# LightLinkV2.net
KiCad netlist of a schematic drawn in Altium Designer
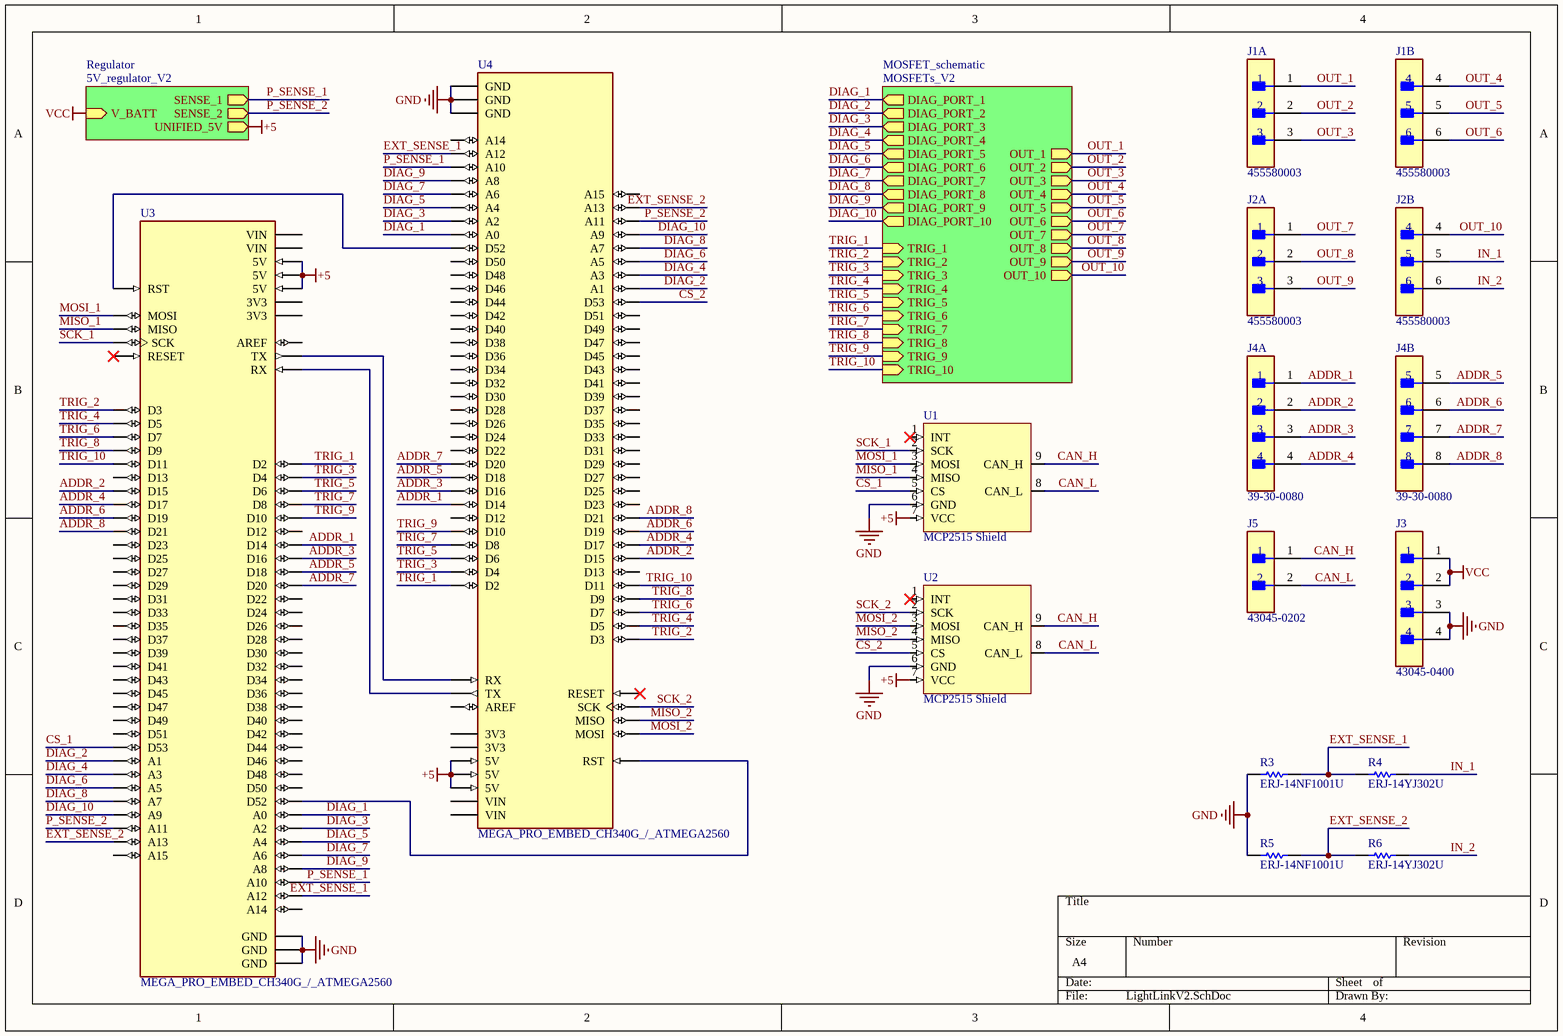
[diagram p0: LightLinkV2.SchDoc]

(export (version "E")
  (design (tool "Eeschema 10.0.6"))
  (components
    (comp (ref "J1")
      (value "455580003")
      (footprint "FP-455580003-MFG")
      (description "Connector Header Through Hole, Right Angle 6 position 0.165\" (4.20mm)")
      (fields (field (name "OCTOPART") "https://octopart.com/45558-0003-molex-7672845"))
      (libsource (lib "Altium Content Vault") (part "bb9cbdb24149a20ba329b4e86909569"))
    )
    (comp (ref "J2")
      (value "455580003")
      (footprint "FP-455580003-MFG")
      (description "Connector Header Through Hole, Right Angle 6 position 0.165\" (4.20mm)")
      (fields (field (name "OCTOPART") "https://octopart.com/45558-0003-molex-7672845"))
      (libsource (lib "Altium Content Vault") (part "bb9cbdb24149a20ba329b4e86909569"))
    )
    (comp (ref "J3")
      (value "43045-0400")
      (footprint "FP-43045-0400-MFG")
      (description "CONN HEADER R/A 4POS 3MM")
      (fields
        (field (name "MANUFACTURER") "Molex")
        (field (name "OCTOPART") "https://octopart.com/43045-0400-molex-287063")
      )
      (libsource (lib "Altium Content Vault") (part "c01754ab0efc13afb7424b896f394ef"))
    )
    (comp (ref "J4")
      (value "39-30-0080")
      (footprint "FP-39-30-0080-MFG")
      (description "CONN HEADER R/A 8POS 4.2MM")
      (libsource (lib "Altium Content Vault") (part "85438c39ca9ef07d43bb2e97c52bc44"))
    )
    (comp (ref "J5")
      (value "43045-0202")
      (footprint "FP-43045-0202-MFG")
      (description "CONN HEADER R/A 2POS")
      (libsource (lib "Altium Content Vault") (part "3bc925449376181038e59eaffc5286c"))
    )
    (comp (ref "R3")
      (value "ERJ-14NF1001U")
      (footprint "RESC3225X70X50NL20T20")
      (fields (field (name "MANUFACTURER") "Panasonic"))
      (libsource (lib "Altium Content Vault") (part "RES"))
    )
    (comp (ref "R4")
      (value "ERJ-14YJ302U")
      (footprint "RESC3225X70X50NL20T20")
      (fields (field (name "MANUFACTURER") "Panasonic"))
      (libsource (lib "Altium Content Vault") (part "RES"))
    )
    (comp (ref "R5")
      (value "ERJ-14NF1001U")
      (footprint "RESC3225X70X50NL20T20")
      (fields (field (name "MANUFACTURER") "Panasonic"))
      (libsource (lib "Altium Content Vault") (part "RES"))
    )
    (comp (ref "R6")
      (value "ERJ-14YJ302U")
      (footprint "RESC3225X70X50NL20T20")
      (fields (field (name "MANUFACTURER") "Panasonic"))
      (libsource (lib "Altium Content Vault") (part "RES"))
    )
    (comp (ref "U1")
      (value "MCP2515 Shield")
      (footprint "MCP2515 Shield-Footprint-1")
      (libsource (lib "uORocketry Hardware") (part "MCP2515 Shield Symbol"))
    )
    (comp (ref "U2")
      (value "MCP2515 Shield")
      (footprint "MCP2515 Shield-Footprint-1")
      (libsource (lib "uORocketry Hardware") (part "MCP2515 Shield Symbol"))
    )
    (comp (ref "U3")
      (value "MEGA_PRO_EMBED_CH340G_/_ATMEGA2560")
      (footprint "MODULE_MEGA_PRO_EMBED_CH340G_/_ATMEGA2560")
      (description "Mega 2560 PRO (Embed) CH340G/ATmega2560-16AU")
      (libsource (lib "uORocketry Hardware") (part "MEGA_PRO_EMBED_CH340G_/_ATMEGA2560"))
    )
    (comp (ref "U4")
      (value "MEGA_PRO_EMBED_CH340G_/_ATMEGA2560")
      (footprint "MODULE_MEGA_PRO_EMBED_CH340G_/_ATMEGA2560")
      (description "Mega 2560 PRO (Embed) CH340G/ATmega2560-16AU")
      (libsource (lib "") (part "MEGA_PRO_EMBED_CH340G_/_ATMEGA2560_1"))
    )
  )
  (nets
    (net (code "1") (name "+5") (class "Default")
      (node (ref "U1") (pin "7") (pinfunction "VCC_7") (pintype "input"))
      (node (ref "U2") (pin "7") (pinfunction "VCC_7") (pintype "input"))
      (node (ref "U3") (pin "5V_1") (pinfunction "5V_5V_1") (pintype "input"))
      (node (ref "U3") (pin "5V_2") (pinfunction "5V_5V_2") (pintype "input"))
      (node (ref "U3") (pin "5V_3") (pinfunction "5V_5V_3") (pintype "input"))
      (node (ref "U4") (pin "5V_1") (pinfunction "5V_5V_1") (pintype "input"))
      (node (ref "U4") (pin "5V_2") (pinfunction "5V_5V_2") (pintype "input"))
      (node (ref "U4") (pin "5V_3") (pinfunction "5V_5V_3") (pintype "input"))
    )
    (net (code "2") (name "/ADDR_1") (class "Default")
      (node (ref "J4") (pin "1") (pinfunction "1_1") (pintype "passive"))
      (node (ref "U3") (pin "D14") (pinfunction "D14_D14") (pintype "bidirectional"))
      (node (ref "U4") (pin "D14") (pinfunction "D14_D14") (pintype "bidirectional"))
    )
    (net (code "3") (name "/ADDR_2") (class "Default")
      (node (ref "J4") (pin "2") (pinfunction "2_2") (pintype "passive"))
      (node (ref "U3") (pin "D15") (pinfunction "D15_D15") (pintype "bidirectional"))
      (node (ref "U4") (pin "D15") (pinfunction "D15_D15") (pintype "bidirectional"))
    )
    (net (code "4") (name "/ADDR_3") (class "Default")
      (node (ref "J4") (pin "3") (pinfunction "3_3") (pintype "passive"))
      (node (ref "U3") (pin "D16") (pinfunction "D16_D16") (pintype "bidirectional"))
      (node (ref "U4") (pin "D16") (pinfunction "D16_D16") (pintype "bidirectional"))
    )
    (net (code "5") (name "/ADDR_4") (class "Default")
      (node (ref "J4") (pin "4") (pinfunction "4_4") (pintype "passive"))
      (node (ref "U3") (pin "D17") (pinfunction "D17_D17") (pintype "bidirectional"))
      (node (ref "U4") (pin "D17") (pinfunction "D17_D17") (pintype "bidirectional"))
    )
    (net (code "6") (name "/ADDR_5") (class "Default")
      (node (ref "J4") (pin "5") (pinfunction "5_5") (pintype "passive"))
      (node (ref "U3") (pin "D18") (pinfunction "D18_D18") (pintype "bidirectional"))
      (node (ref "U4") (pin "D18") (pinfunction "D18_D18") (pintype "bidirectional"))
    )
    (net (code "7") (name "/ADDR_6") (class "Default")
      (node (ref "J4") (pin "6") (pinfunction "6_6") (pintype "passive"))
      (node (ref "U3") (pin "D19") (pinfunction "D19_D19") (pintype "bidirectional"))
      (node (ref "U4") (pin "D19") (pinfunction "D19_D19") (pintype "bidirectional"))
    )
    (net (code "8") (name "/ADDR_7") (class "Default")
      (node (ref "J4") (pin "7") (pinfunction "7_7") (pintype "passive"))
      (node (ref "U3") (pin "D20") (pinfunction "D20_D20") (pintype "bidirectional"))
      (node (ref "U4") (pin "D20") (pinfunction "D20_D20") (pintype "bidirectional"))
    )
    (net (code "9") (name "/ADDR_8") (class "Default")
      (node (ref "J4") (pin "8") (pinfunction "8_8") (pintype "passive"))
      (node (ref "U3") (pin "D21") (pinfunction "D21_D21") (pintype "bidirectional"))
      (node (ref "U4") (pin "D21") (pinfunction "D21_D21") (pintype "bidirectional"))
    )
    (net (code "10") (name "/CAN_H") (class "Default")
      (node (ref "J5") (pin "1") (pinfunction "1_1") (pintype "passive"))
      (node (ref "U1") (pin "9") (pinfunction "CAN_H_9") (pintype "bidirectional"))
      (node (ref "U2") (pin "9") (pinfunction "CAN_H_9") (pintype "bidirectional"))
    )
    (net (code "11") (name "/CAN_L") (class "Default")
      (node (ref "J5") (pin "2") (pinfunction "2_2") (pintype "passive"))
      (node (ref "U1") (pin "8") (pinfunction "CAN_L_8") (pintype "bidirectional"))
      (node (ref "U2") (pin "8") (pinfunction "CAN_L_8") (pintype "bidirectional"))
    )
    (net (code "12") (name "/CS_1") (class "Default")
      (node (ref "U1") (pin "5") (pinfunction "CS_5") (pintype "input"))
      (node (ref "U3") (pin "D53") (pinfunction "D53_D53") (pintype "bidirectional"))
    )
    (net (code "13") (name "/CS_2") (class "Default")
      (node (ref "U2") (pin "5") (pinfunction "CS_5") (pintype "input"))
      (node (ref "U4") (pin "D53") (pinfunction "D53_D53") (pintype "bidirectional"))
    )
    (net (code "14") (name "/DIAG_1") (class "Default")
      (node (ref "U3") (pin "A0") (pinfunction "A0_A0") (pintype "bidirectional"))
      (node (ref "U4") (pin "A0") (pinfunction "A0_A0") (pintype "bidirectional"))
    )
    (net (code "15") (name "/DIAG_2") (class "Default")
      (node (ref "U3") (pin "A1") (pinfunction "A1_A1") (pintype "bidirectional"))
      (node (ref "U4") (pin "A1") (pinfunction "A1_A1") (pintype "bidirectional"))
    )
    (net (code "16") (name "/DIAG_3") (class "Default")
      (node (ref "U3") (pin "A2") (pinfunction "A2_A2") (pintype "bidirectional"))
      (node (ref "U4") (pin "A2") (pinfunction "A2_A2") (pintype "bidirectional"))
    )
    (net (code "17") (name "/DIAG_4") (class "Default")
      (node (ref "U3") (pin "A3") (pinfunction "A3_A3") (pintype "bidirectional"))
      (node (ref "U4") (pin "A3") (pinfunction "A3_A3") (pintype "bidirectional"))
    )
    (net (code "18") (name "/DIAG_5") (class "Default")
      (node (ref "U3") (pin "A4") (pinfunction "A4_A4") (pintype "bidirectional"))
      (node (ref "U4") (pin "A4") (pinfunction "A4_A4") (pintype "bidirectional"))
    )
    (net (code "19") (name "/DIAG_6") (class "Default")
      (node (ref "U3") (pin "A5") (pinfunction "A5_A5") (pintype "bidirectional"))
      (node (ref "U4") (pin "A5") (pinfunction "A5_A5") (pintype "bidirectional"))
    )
    (net (code "20") (name "/DIAG_7") (class "Default")
      (node (ref "U3") (pin "A6") (pinfunction "A6_A6") (pintype "bidirectional"))
      (node (ref "U4") (pin "A6") (pinfunction "A6_A6") (pintype "bidirectional"))
    )
    (net (code "21") (name "/DIAG_8") (class "Default")
      (node (ref "U3") (pin "A7") (pinfunction "A7_A7") (pintype "bidirectional"))
      (node (ref "U4") (pin "A7") (pinfunction "A7_A7") (pintype "bidirectional"))
    )
    (net (code "22") (name "/DIAG_9") (class "Default")
      (node (ref "U3") (pin "A8") (pinfunction "A8_A8") (pintype "bidirectional"))
      (node (ref "U4") (pin "A8") (pinfunction "A8_A8") (pintype "bidirectional"))
    )
    (net (code "23") (name "/DIAG_10") (class "Default")
      (node (ref "U3") (pin "A9") (pinfunction "A9_A9") (pintype "bidirectional"))
      (node (ref "U4") (pin "A9") (pinfunction "A9_A9") (pintype "bidirectional"))
    )
    (net (code "24") (name "/EXT_SENSE_1") (class "Default")
      (node (ref "R3") (pin "2") (pinfunction "2_2") (pintype "passive"))
      (node (ref "R4") (pin "1") (pinfunction "1_1") (pintype "passive"))
      (node (ref "U3") (pin "A12") (pinfunction "A12_A12") (pintype "bidirectional"))
      (node (ref "U4") (pin "A12") (pinfunction "A12_A12") (pintype "bidirectional"))
    )
    (net (code "25") (name "/EXT_SENSE_2") (class "Default")
      (node (ref "R5") (pin "2") (pinfunction "2_2") (pintype "passive"))
      (node (ref "R6") (pin "1") (pinfunction "1_1") (pintype "passive"))
      (node (ref "U3") (pin "A13") (pinfunction "A13_A13") (pintype "bidirectional"))
      (node (ref "U4") (pin "A13") (pinfunction "A13_A13") (pintype "bidirectional"))
    )
    (net (code "26") (name "/IN_1") (class "Default")
      (node (ref "J2") (pin "5") (pinfunction "5_5") (pintype "passive"))
      (node (ref "R4") (pin "2") (pinfunction "2_2") (pintype "passive"))
    )
    (net (code "27") (name "/IN_2") (class "Default")
      (node (ref "J2") (pin "6") (pinfunction "6_6") (pintype "passive"))
      (node (ref "R6") (pin "2") (pinfunction "2_2") (pintype "passive"))
    )
    (net (code "28") (name "/MISO_1") (class "Default")
      (node (ref "U1") (pin "4") (pinfunction "MISO_4") (pintype "input"))
      (node (ref "U3") (pin "MISO") (pinfunction "MISO_MISO") (pintype "bidirectional"))
    )
    (net (code "29") (name "/MISO_2") (class "Default")
      (node (ref "U2") (pin "4") (pinfunction "MISO_4") (pintype "input"))
      (node (ref "U4") (pin "MISO") (pinfunction "MISO_MISO") (pintype "bidirectional"))
    )
    (net (code "30") (name "/MOSI_1") (class "Default")
      (node (ref "U1") (pin "3") (pinfunction "MOSI_3") (pintype "input"))
      (node (ref "U3") (pin "MOSI") (pinfunction "MOSI_MOSI") (pintype "bidirectional"))
    )
    (net (code "31") (name "/MOSI_2") (class "Default")
      (node (ref "U2") (pin "3") (pinfunction "MOSI_3") (pintype "input"))
      (node (ref "U4") (pin "MOSI") (pinfunction "MOSI_MOSI") (pintype "bidirectional"))
    )
    (net (code "32") (name "/OUT_1") (class "Default")
      (node (ref "J1") (pin "1") (pinfunction "1_1") (pintype "passive"))
    )
    (net (code "33") (name "/OUT_2") (class "Default")
      (node (ref "J1") (pin "2") (pinfunction "2_2") (pintype "passive"))
    )
    (net (code "34") (name "/OUT_3") (class "Default")
      (node (ref "J1") (pin "3") (pinfunction "3_3") (pintype "passive"))
    )
    (net (code "35") (name "/OUT_4") (class "Default")
      (node (ref "J1") (pin "4") (pinfunction "4_4") (pintype "passive"))
    )
    (net (code "36") (name "/OUT_5") (class "Default")
      (node (ref "J1") (pin "5") (pinfunction "5_5") (pintype "passive"))
    )
    (net (code "37") (name "/OUT_6") (class "Default")
      (node (ref "J1") (pin "6") (pinfunction "6_6") (pintype "passive"))
    )
    (net (code "38") (name "/OUT_7") (class "Default")
      (node (ref "J2") (pin "1") (pinfunction "1_1") (pintype "passive"))
    )
    (net (code "39") (name "/OUT_8") (class "Default")
      (node (ref "J2") (pin "2") (pinfunction "2_2") (pintype "passive"))
    )
    (net (code "40") (name "/OUT_9") (class "Default")
      (node (ref "J2") (pin "3") (pinfunction "3_3") (pintype "passive"))
    )
    (net (code "41") (name "/OUT_10") (class "Default")
      (node (ref "J2") (pin "4") (pinfunction "4_4") (pintype "passive"))
    )
    (net (code "42") (name "/P_SENSE_1") (class "Default")
      (node (ref "U3") (pin "A10") (pinfunction "A10_A10") (pintype "bidirectional"))
      (node (ref "U4") (pin "A10") (pinfunction "A10_A10") (pintype "bidirectional"))
    )
    (net (code "43") (name "/P_SENSE_2") (class "Default")
      (node (ref "U3") (pin "A11") (pinfunction "A11_A11") (pintype "bidirectional"))
      (node (ref "U4") (pin "A11") (pinfunction "A11_A11") (pintype "bidirectional"))
    )
    (net (code "44") (name "/SCK_1") (class "Default")
      (node (ref "U1") (pin "2") (pinfunction "SCK_2") (pintype "input"))
      (node (ref "U3") (pin "SCK") (pinfunction "SCK_SCK") (pintype "bidirectional"))
    )
    (net (code "45") (name "/SCK_2") (class "Default")
      (node (ref "U2") (pin "2") (pinfunction "SCK_2") (pintype "input"))
      (node (ref "U4") (pin "SCK") (pinfunction "SCK_SCK") (pintype "bidirectional"))
    )
    (net (code "46") (name "/TRIG_1") (class "Default")
      (node (ref "U3") (pin "D2") (pinfunction "D2_D2") (pintype "bidirectional"))
      (node (ref "U4") (pin "D2") (pinfunction "D2_D2") (pintype "bidirectional"))
    )
    (net (code "47") (name "/TRIG_2") (class "Default")
      (node (ref "U3") (pin "D3") (pinfunction "D3_D3") (pintype "bidirectional"))
      (node (ref "U4") (pin "D3") (pinfunction "D3_D3") (pintype "bidirectional"))
    )
    (net (code "48") (name "/TRIG_3") (class "Default")
      (node (ref "U3") (pin "D4") (pinfunction "D4_D4") (pintype "bidirectional"))
      (node (ref "U4") (pin "D4") (pinfunction "D4_D4") (pintype "bidirectional"))
    )
    (net (code "49") (name "/TRIG_4") (class "Default")
      (node (ref "U3") (pin "D5") (pinfunction "D5_D5") (pintype "bidirectional"))
      (node (ref "U4") (pin "D5") (pinfunction "D5_D5") (pintype "bidirectional"))
    )
    (net (code "50") (name "/TRIG_5") (class "Default")
      (node (ref "U3") (pin "D6") (pinfunction "D6_D6") (pintype "bidirectional"))
      (node (ref "U4") (pin "D6") (pinfunction "D6_D6") (pintype "bidirectional"))
    )
    (net (code "51") (name "/TRIG_6") (class "Default")
      (node (ref "U3") (pin "D7") (pinfunction "D7_D7") (pintype "bidirectional"))
      (node (ref "U4") (pin "D7") (pinfunction "D7_D7") (pintype "bidirectional"))
    )
    (net (code "52") (name "/TRIG_7") (class "Default")
      (node (ref "U3") (pin "D8") (pinfunction "D8_D8") (pintype "bidirectional"))
      (node (ref "U4") (pin "D8") (pinfunction "D8_D8") (pintype "bidirectional"))
    )
    (net (code "53") (name "/TRIG_8") (class "Default")
      (node (ref "U3") (pin "D9") (pinfunction "D9_D9") (pintype "bidirectional"))
      (node (ref "U4") (pin "D9") (pinfunction "D9_D9") (pintype "bidirectional"))
    )
    (net (code "54") (name "/TRIG_9") (class "Default")
      (node (ref "U3") (pin "D10") (pinfunction "D10_D10") (pintype "bidirectional"))
      (node (ref "U4") (pin "D10") (pinfunction "D10_D10") (pintype "bidirectional"))
    )
    (net (code "55") (name "/TRIG_10") (class "Default")
      (node (ref "U3") (pin "D11") (pinfunction "D11_D11") (pintype "bidirectional"))
      (node (ref "U4") (pin "D11") (pinfunction "D11_D11") (pintype "bidirectional"))
    )
    (net (code "56") (name "GND") (class "Default")
      (node (ref "J3") (pin "3") (pinfunction "3_3") (pintype "passive"))
      (node (ref "J3") (pin "4") (pinfunction "4_4") (pintype "passive"))
      (node (ref "R3") (pin "1") (pinfunction "1_1") (pintype "passive"))
      (node (ref "R5") (pin "1") (pinfunction "1_1") (pintype "passive"))
      (node (ref "U1") (pin "6") (pinfunction "GND_6") (pintype "input"))
      (node (ref "U2") (pin "6") (pinfunction "GND_6") (pintype "input"))
      (node (ref "U3") (pin "GND_1") (pinfunction "GND_GND_1") (pintype "power_in"))
      (node (ref "U3") (pin "GND_2") (pinfunction "GND_GND_2") (pintype "power_in"))
      (node (ref "U3") (pin "GND_3") (pinfunction "GND_GND_3") (pintype "power_in"))
      (node (ref "U4") (pin "GND_1") (pinfunction "GND_GND_1") (pintype "power_in"))
      (node (ref "U4") (pin "GND_2") (pinfunction "GND_GND_2") (pintype "power_in"))
      (node (ref "U4") (pin "GND_3") (pinfunction "GND_GND_3") (pintype "power_in"))
    )
    (net (code "57") (name "Net-(U3-PadD52)") (class "Default")
      (node (ref "U3") (pin "D52") (pinfunction "D52_D52") (pintype "bidirectional"))
      (node (ref "U4") (pin "RST") (pinfunction "RST_RST") (pintype "input"))
    )
    (net (code "58") (name "Net-(U3-PadRST)") (class "Default")
      (node (ref "U3") (pin "RST") (pinfunction "RST_RST") (pintype "input"))
      (node (ref "U4") (pin "D52") (pinfunction "D52_D52") (pintype "bidirectional"))
    )
    (net (code "59") (name "Net-(U3-PadRX)") (class "Default")
      (node (ref "U3") (pin "RX") (pinfunction "RX_RX") (pintype "input"))
      (node (ref "U4") (pin "TX") (pinfunction "TX_TX") (pintype "output"))
    )
    (net (code "60") (name "Net-(U3-PadTX)") (class "Default")
      (node (ref "U3") (pin "TX") (pinfunction "TX_TX") (pintype "output"))
      (node (ref "U4") (pin "RX") (pinfunction "RX_RX") (pintype "input"))
    )
    (net (code "61") (name "VCC") (class "Default")
      (node (ref "J3") (pin "1") (pinfunction "1_1") (pintype "passive"))
      (node (ref "J3") (pin "2") (pinfunction "2_2") (pintype "passive"))
    )
    (net (code "62") (name "unconnected-(U1-INT-Pad1)") (class "Default")
      (node (ref "U1") (pin "1") (pinfunction "INT_1") (pintype "input+no_connect"))
    )
    (net (code "63") (name "unconnected-(U2-INT-Pad1)") (class "Default")
      (node (ref "U2") (pin "1") (pinfunction "INT_1") (pintype "input+no_connect"))
    )
    (net (code "64") (name "unconnected-(U3-3V3-Pad3V3_1)") (class "Default")
      (node (ref "U3") (pin "3V3_1") (pinfunction "3V3_3V3_1") (pintype "power_in"))
    )
    (net (code "65") (name "unconnected-(U3-3V3-Pad3V3_2)") (class "Default")
      (node (ref "U3") (pin "3V3_2") (pinfunction "3V3_3V3_2") (pintype "power_in"))
    )
    (net (code "66") (name "unconnected-(U3-PadA14)") (class "Default")
      (node (ref "U3") (pin "A14") (pinfunction "A14_A14") (pintype "bidirectional"))
    )
    (net (code "67") (name "unconnected-(U3-PadA15)") (class "Default")
      (node (ref "U3") (pin "A15") (pinfunction "A15_A15") (pintype "bidirectional"))
    )
    (net (code "68") (name "unconnected-(U3-PadAREF)") (class "Default")
      (node (ref "U3") (pin "AREF") (pinfunction "AREF_AREF") (pintype "bidirectional"))
    )
    (net (code "69") (name "unconnected-(U3-PadD12)") (class "Default")
      (node (ref "U3") (pin "D12") (pinfunction "D12_D12") (pintype "bidirectional"))
    )
    (net (code "70") (name "unconnected-(U3-PadD13)") (class "Default")
      (node (ref "U3") (pin "D13") (pinfunction "D13_D13") (pintype "bidirectional"))
    )
    (net (code "71") (name "unconnected-(U3-PadD22)") (class "Default")
      (node (ref "U3") (pin "D22") (pinfunction "D22_D22") (pintype "bidirectional"))
    )
    (net (code "72") (name "unconnected-(U3-PadD23)") (class "Default")
      (node (ref "U3") (pin "D23") (pinfunction "D23_D23") (pintype "bidirectional"))
    )
    (net (code "73") (name "unconnected-(U3-PadD24)") (class "Default")
      (node (ref "U3") (pin "D24") (pinfunction "D24_D24") (pintype "bidirectional"))
    )
    (net (code "74") (name "unconnected-(U3-PadD25)") (class "Default")
      (node (ref "U3") (pin "D25") (pinfunction "D25_D25") (pintype "bidirectional"))
    )
    (net (code "75") (name "unconnected-(U3-PadD26)") (class "Default")
      (node (ref "U3") (pin "D26") (pinfunction "D26_D26") (pintype "bidirectional"))
    )
    (net (code "76") (name "unconnected-(U3-PadD27)") (class "Default")
      (node (ref "U3") (pin "D27") (pinfunction "D27_D27") (pintype "bidirectional"))
    )
    (net (code "77") (name "unconnected-(U3-PadD28)") (class "Default")
      (node (ref "U3") (pin "D28") (pinfunction "D28_D28") (pintype "bidirectional"))
    )
    (net (code "78") (name "unconnected-(U3-PadD29)") (class "Default")
      (node (ref "U3") (pin "D29") (pinfunction "D29_D29") (pintype "bidirectional"))
    )
    (net (code "79") (name "unconnected-(U3-PadD30)") (class "Default")
      (node (ref "U3") (pin "D30") (pinfunction "D30_D30") (pintype "bidirectional"))
    )
    (net (code "80") (name "unconnected-(U3-PadD31)") (class "Default")
      (node (ref "U3") (pin "D31") (pinfunction "D31_D31") (pintype "bidirectional"))
    )
    (net (code "81") (name "unconnected-(U3-PadD32)") (class "Default")
      (node (ref "U3") (pin "D32") (pinfunction "D32_D32") (pintype "bidirectional"))
    )
    (net (code "82") (name "unconnected-(U3-PadD33)") (class "Default")
      (node (ref "U3") (pin "D33") (pinfunction "D33_D33") (pintype "bidirectional"))
    )
    (net (code "83") (name "unconnected-(U3-PadD34)") (class "Default")
      (node (ref "U3") (pin "D34") (pinfunction "D34_D34") (pintype "bidirectional"))
    )
    (net (code "84") (name "unconnected-(U3-PadD35)") (class "Default")
      (node (ref "U3") (pin "D35") (pinfunction "D35_D35") (pintype "bidirectional"))
    )
    (net (code "85") (name "unconnected-(U3-PadD36)") (class "Default")
      (node (ref "U3") (pin "D36") (pinfunction "D36_D36") (pintype "bidirectional"))
    )
    (net (code "86") (name "unconnected-(U3-PadD37)") (class "Default")
      (node (ref "U3") (pin "D37") (pinfunction "D37_D37") (pintype "bidirectional"))
    )
    (net (code "87") (name "unconnected-(U3-PadD38)") (class "Default")
      (node (ref "U3") (pin "D38") (pinfunction "D38_D38") (pintype "bidirectional"))
    )
    (net (code "88") (name "unconnected-(U3-PadD39)") (class "Default")
      (node (ref "U3") (pin "D39") (pinfunction "D39_D39") (pintype "bidirectional"))
    )
    (net (code "89") (name "unconnected-(U3-PadD40)") (class "Default")
      (node (ref "U3") (pin "D40") (pinfunction "D40_D40") (pintype "bidirectional"))
    )
    (net (code "90") (name "unconnected-(U3-PadD41)") (class "Default")
      (node (ref "U3") (pin "D41") (pinfunction "D41_D41") (pintype "bidirectional"))
    )
    (net (code "91") (name "unconnected-(U3-PadD42)") (class "Default")
      (node (ref "U3") (pin "D42") (pinfunction "D42_D42") (pintype "bidirectional"))
    )
    (net (code "92") (name "unconnected-(U3-PadD43)") (class "Default")
      (node (ref "U3") (pin "D43") (pinfunction "D43_D43") (pintype "bidirectional"))
    )
    (net (code "93") (name "unconnected-(U3-PadD44)") (class "Default")
      (node (ref "U3") (pin "D44") (pinfunction "D44_D44") (pintype "bidirectional"))
    )
    (net (code "94") (name "unconnected-(U3-PadD45)") (class "Default")
      (node (ref "U3") (pin "D45") (pinfunction "D45_D45") (pintype "bidirectional"))
    )
    (net (code "95") (name "unconnected-(U3-PadD46)") (class "Default")
      (node (ref "U3") (pin "D46") (pinfunction "D46_D46") (pintype "bidirectional"))
    )
    (net (code "96") (name "unconnected-(U3-PadD47)") (class "Default")
      (node (ref "U3") (pin "D47") (pinfunction "D47_D47") (pintype "bidirectional"))
    )
    (net (code "97") (name "unconnected-(U3-PadD48)") (class "Default")
      (node (ref "U3") (pin "D48") (pinfunction "D48_D48") (pintype "bidirectional"))
    )
    (net (code "98") (name "unconnected-(U3-PadD49)") (class "Default")
      (node (ref "U3") (pin "D49") (pinfunction "D49_D49") (pintype "bidirectional"))
    )
    (net (code "99") (name "unconnected-(U3-PadD50)") (class "Default")
      (node (ref "U3") (pin "D50") (pinfunction "D50_D50") (pintype "bidirectional"))
    )
    (net (code "100") (name "unconnected-(U3-PadD51)") (class "Default")
      (node (ref "U3") (pin "D51") (pinfunction "D51_D51") (pintype "bidirectional"))
    )
    (net (code "101") (name "unconnected-(U3-PadRESET)") (class "Default")
      (node (ref "U3") (pin "RESET") (pinfunction "RESET_RESET") (pintype "input+no_connect"))
    )
    (net (code "102") (name "unconnected-(U3-VIN-PadVIN_1)") (class "Default")
      (node (ref "U3") (pin "VIN_1") (pinfunction "VIN_VIN_1") (pintype "power_in"))
    )
    (net (code "103") (name "unconnected-(U3-VIN-PadVIN_2)") (class "Default")
      (node (ref "U3") (pin "VIN_2") (pinfunction "VIN_VIN_2") (pintype "power_in"))
    )
    (net (code "104") (name "unconnected-(U4-3V3-Pad3V3_1)") (class "Default")
      (node (ref "U4") (pin "3V3_1") (pinfunction "3V3_3V3_1") (pintype "power_in"))
    )
    (net (code "105") (name "unconnected-(U4-3V3-Pad3V3_2)") (class "Default")
      (node (ref "U4") (pin "3V3_2") (pinfunction "3V3_3V3_2") (pintype "power_in"))
    )
    (net (code "106") (name "unconnected-(U4-PadA14)") (class "Default")
      (node (ref "U4") (pin "A14") (pinfunction "A14_A14") (pintype "bidirectional"))
    )
    (net (code "107") (name "unconnected-(U4-PadA15)") (class "Default")
      (node (ref "U4") (pin "A15") (pinfunction "A15_A15") (pintype "bidirectional"))
    )
    (net (code "108") (name "unconnected-(U4-PadAREF)") (class "Default")
      (node (ref "U4") (pin "AREF") (pinfunction "AREF_AREF") (pintype "bidirectional"))
    )
    (net (code "109") (name "unconnected-(U4-PadD12)") (class "Default")
      (node (ref "U4") (pin "D12") (pinfunction "D12_D12") (pintype "bidirectional"))
    )
    (net (code "110") (name "unconnected-(U4-PadD13)") (class "Default")
      (node (ref "U4") (pin "D13") (pinfunction "D13_D13") (pintype "bidirectional"))
    )
    (net (code "111") (name "unconnected-(U4-PadD22)") (class "Default")
      (node (ref "U4") (pin "D22") (pinfunction "D22_D22") (pintype "bidirectional"))
    )
    (net (code "112") (name "unconnected-(U4-PadD23)") (class "Default")
      (node (ref "U4") (pin "D23") (pinfunction "D23_D23") (pintype "bidirectional"))
    )
    (net (code "113") (name "unconnected-(U4-PadD24)") (class "Default")
      (node (ref "U4") (pin "D24") (pinfunction "D24_D24") (pintype "bidirectional"))
    )
    (net (code "114") (name "unconnected-(U4-PadD25)") (class "Default")
      (node (ref "U4") (pin "D25") (pinfunction "D25_D25") (pintype "bidirectional"))
    )
    (net (code "115") (name "unconnected-(U4-PadD26)") (class "Default")
      (node (ref "U4") (pin "D26") (pinfunction "D26_D26") (pintype "bidirectional"))
    )
    (net (code "116") (name "unconnected-(U4-PadD27)") (class "Default")
      (node (ref "U4") (pin "D27") (pinfunction "D27_D27") (pintype "bidirectional"))
    )
    (net (code "117") (name "unconnected-(U4-PadD28)") (class "Default")
      (node (ref "U4") (pin "D28") (pinfunction "D28_D28") (pintype "bidirectional"))
    )
    (net (code "118") (name "unconnected-(U4-PadD29)") (class "Default")
      (node (ref "U4") (pin "D29") (pinfunction "D29_D29") (pintype "bidirectional"))
    )
    (net (code "119") (name "unconnected-(U4-PadD30)") (class "Default")
      (node (ref "U4") (pin "D30") (pinfunction "D30_D30") (pintype "bidirectional"))
    )
    (net (code "120") (name "unconnected-(U4-PadD31)") (class "Default")
      (node (ref "U4") (pin "D31") (pinfunction "D31_D31") (pintype "bidirectional"))
    )
    (net (code "121") (name "unconnected-(U4-PadD32)") (class "Default")
      (node (ref "U4") (pin "D32") (pinfunction "D32_D32") (pintype "bidirectional"))
    )
    (net (code "122") (name "unconnected-(U4-PadD33)") (class "Default")
      (node (ref "U4") (pin "D33") (pinfunction "D33_D33") (pintype "bidirectional"))
    )
    (net (code "123") (name "unconnected-(U4-PadD34)") (class "Default")
      (node (ref "U4") (pin "D34") (pinfunction "D34_D34") (pintype "bidirectional"))
    )
    (net (code "124") (name "unconnected-(U4-PadD35)") (class "Default")
      (node (ref "U4") (pin "D35") (pinfunction "D35_D35") (pintype "bidirectional"))
    )
    (net (code "125") (name "unconnected-(U4-PadD36)") (class "Default")
      (node (ref "U4") (pin "D36") (pinfunction "D36_D36") (pintype "bidirectional"))
    )
    (net (code "126") (name "unconnected-(U4-PadD37)") (class "Default")
      (node (ref "U4") (pin "D37") (pinfunction "D37_D37") (pintype "bidirectional"))
    )
    (net (code "127") (name "unconnected-(U4-PadD38)") (class "Default")
      (node (ref "U4") (pin "D38") (pinfunction "D38_D38") (pintype "bidirectional"))
    )
    (net (code "128") (name "unconnected-(U4-PadD39)") (class "Default")
      (node (ref "U4") (pin "D39") (pinfunction "D39_D39") (pintype "bidirectional"))
    )
    (net (code "129") (name "unconnected-(U4-PadD40)") (class "Default")
      (node (ref "U4") (pin "D40") (pinfunction "D40_D40") (pintype "bidirectional"))
    )
    (net (code "130") (name "unconnected-(U4-PadD41)") (class "Default")
      (node (ref "U4") (pin "D41") (pinfunction "D41_D41") (pintype "bidirectional"))
    )
    (net (code "131") (name "unconnected-(U4-PadD42)") (class "Default")
      (node (ref "U4") (pin "D42") (pinfunction "D42_D42") (pintype "bidirectional"))
    )
    (net (code "132") (name "unconnected-(U4-PadD43)") (class "Default")
      (node (ref "U4") (pin "D43") (pinfunction "D43_D43") (pintype "bidirectional"))
    )
    (net (code "133") (name "unconnected-(U4-PadD44)") (class "Default")
      (node (ref "U4") (pin "D44") (pinfunction "D44_D44") (pintype "bidirectional"))
    )
    (net (code "134") (name "unconnected-(U4-PadD45)") (class "Default")
      (node (ref "U4") (pin "D45") (pinfunction "D45_D45") (pintype "bidirectional"))
    )
    (net (code "135") (name "unconnected-(U4-PadD46)") (class "Default")
      (node (ref "U4") (pin "D46") (pinfunction "D46_D46") (pintype "bidirectional"))
    )
    (net (code "136") (name "unconnected-(U4-PadD47)") (class "Default")
      (node (ref "U4") (pin "D47") (pinfunction "D47_D47") (pintype "bidirectional"))
    )
    (net (code "137") (name "unconnected-(U4-PadD48)") (class "Default")
      (node (ref "U4") (pin "D48") (pinfunction "D48_D48") (pintype "bidirectional"))
    )
    (net (code "138") (name "unconnected-(U4-PadD49)") (class "Default")
      (node (ref "U4") (pin "D49") (pinfunction "D49_D49") (pintype "bidirectional"))
    )
    (net (code "139") (name "unconnected-(U4-PadD50)") (class "Default")
      (node (ref "U4") (pin "D50") (pinfunction "D50_D50") (pintype "bidirectional"))
    )
    (net (code "140") (name "unconnected-(U4-PadD51)") (class "Default")
      (node (ref "U4") (pin "D51") (pinfunction "D51_D51") (pintype "bidirectional"))
    )
    (net (code "141") (name "unconnected-(U4-PadRESET)") (class "Default")
      (node (ref "U4") (pin "RESET") (pinfunction "RESET_RESET") (pintype "input+no_connect"))
    )
    (net (code "142") (name "unconnected-(U4-VIN-PadVIN_1)") (class "Default")
      (node (ref "U4") (pin "VIN_1") (pinfunction "VIN_VIN_1") (pintype "power_in"))
    )
    (net (code "143") (name "unconnected-(U4-VIN-PadVIN_2)") (class "Default")
      (node (ref "U4") (pin "VIN_2") (pinfunction "VIN_VIN_2") (pintype "power_in"))
    )
  )
)
